# Midi_to_CV.net
KiCad netlist of a schematic drawn in Altium Designer
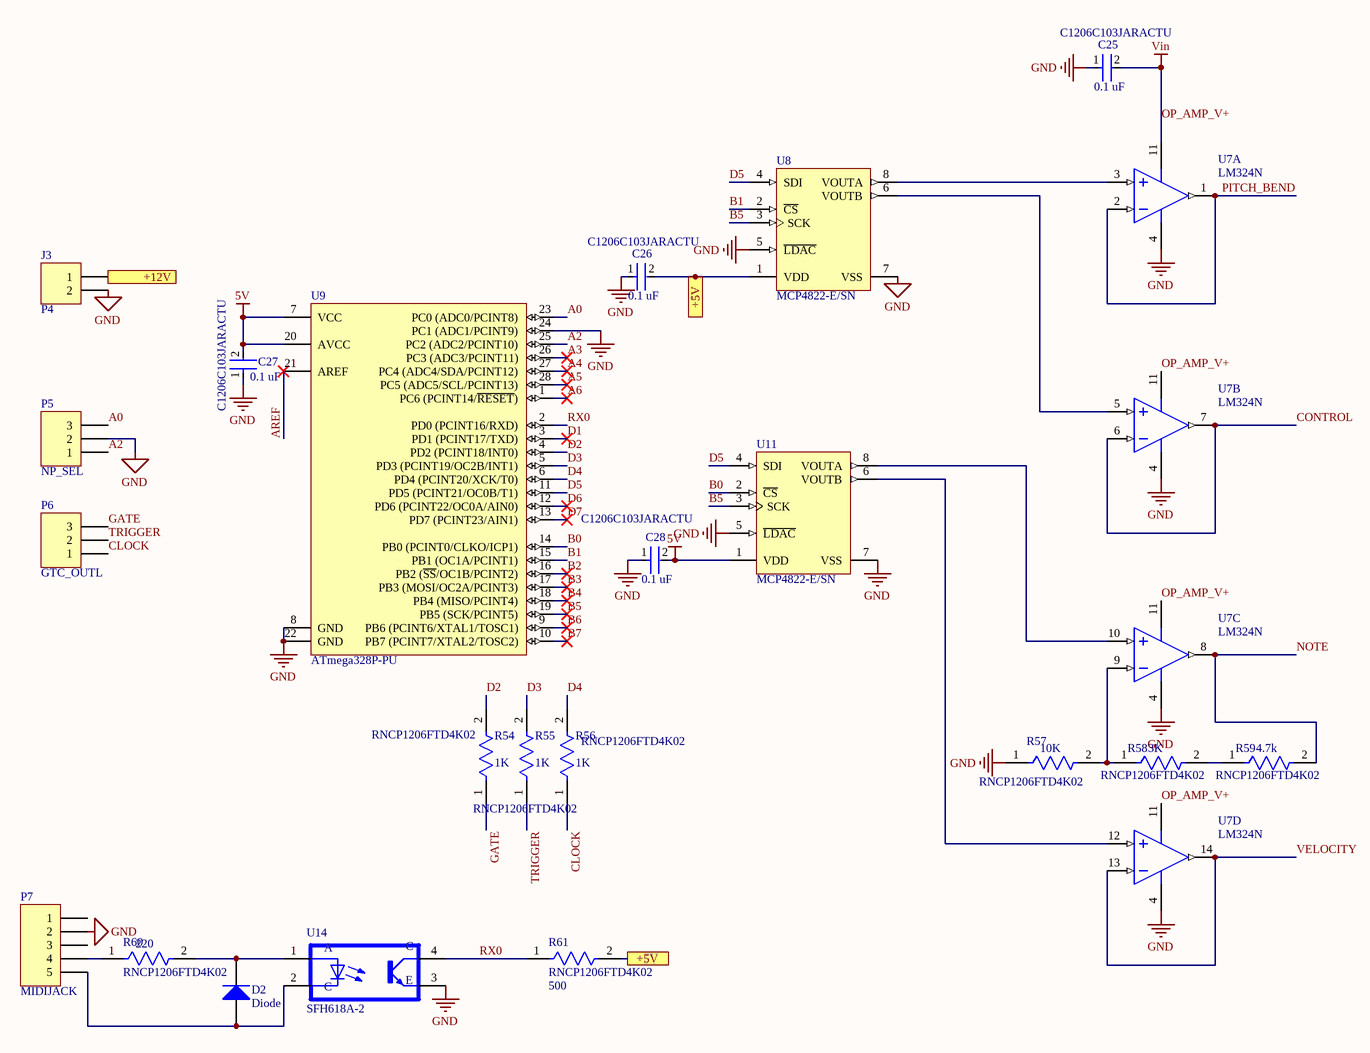
[diagram p0: Midi_to_CV.SchDoc]

(export (version "E")
  (design (tool "Eeschema 10.0.6"))
  (components
    (comp (ref "C25")
      (value "C1206C103JARACTU")
      (footprint "C1206")
      (description "CAP CER 10000PF 250V 5% X7R 1206")
      (fields
        (field (name "TOLERANCE") "0.05")
        (field (name "CAPACITANCE") "0.1 uF")
        (field (name "OCTOPART") "https://octopart.com/c1206c103jaractu-kemet-17306149")
      )
      (libsource (lib "Miscellaneous Devices") (part "b4654b650e69147ec39a6b967a45e02"))
    )
    (comp (ref "C26")
      (value "C1206C103JARACTU")
      (footprint "C1206")
      (description "CAP CER 10000PF 250V 5% X7R 1206")
      (fields
        (field (name "TOLERANCE") "0.05")
        (field (name "CAPACITANCE") "0.1 uF")
        (field (name "OCTOPART") "https://octopart.com/c1206c103jaractu-kemet-17306149")
      )
      (libsource (lib "Miscellaneous Devices") (part "b4654b650e69147ec39a6b967a45e02"))
    )
    (comp (ref "C27")
      (value "C1206C103JARACTU")
      (footprint "C1206")
      (description "CAP CER 10000PF 250V 5% X7R 1206")
      (fields
        (field (name "TOLERANCE") "0.05")
        (field (name "CAPACITANCE") "0.1 uF")
        (field (name "OCTOPART") "https://octopart.com/c1206c103jaractu-kemet-17306149")
      )
      (libsource (lib "Miscellaneous Devices") (part "b4654b650e69147ec39a6b967a45e02"))
    )
    (comp (ref "C28")
      (value "C1206C103JARACTU")
      (footprint "C1206")
      (description "CAP CER 10000PF 250V 5% X7R 1206")
      (fields
        (field (name "TOLERANCE") "0.05")
        (field (name "CAPACITANCE") "0.1 uF")
        (field (name "OCTOPART") "https://octopart.com/c1206c103jaractu-kemet-17306149")
      )
      (libsource (lib "Miscellaneous Devices") (part "b4654b650e69147ec39a6b967a45e02"))
    )
    (comp (ref "D2")
      (value "Diode")
      (footprint "DIODE-0.4")
      (description "Default Diode")
      (fields (field (name "PUBLISHER") "Altium Limited"))
      (libsource (lib "Miscellaneous Devices") (part "Diode"))
    )
    (comp (ref "P4")
      (value "J3")
      (footprint "HDR1X2")
      (description "Header, 2-Pin")
      (fields (field (name "PUBLISHER") "Altium Limited"))
      (libsource (lib "Miscellaneous Connectors") (part "Header 2"))
    )
    (comp (ref "P5")
      (value "NP_SEL")
      (footprint "HDR1X3")
      (description "Header, 3-Pin")
      (fields (field (name "PUBLISHER") "Altium Limited"))
      (libsource (lib "Miscellaneous Connectors") (part "Header 3"))
    )
    (comp (ref "P6")
      (value "GTC_OUTL")
      (footprint "HDR1X3")
      (description "Header, 3-Pin")
      (fields (field (name "PUBLISHER") "Altium Limited"))
      (libsource (lib "Miscellaneous Connectors") (part "Header 3"))
    )
    (comp (ref "P7")
      (value "MIDIJACK")
      (footprint "HDR1X5")
      (description "Header, 5-Pin")
      (fields (field (name "PUBLISHER") "Altium Limited"))
      (libsource (lib "Miscellaneous Connectors") (part "Header 5"))
    )
    (comp (ref "R54")
      (value "RNCP1206FTD4K02")
      (footprint "C1206")
      (description "4.02kΩ ±1% 0.5W 1206 High Power Anti-Sulfur Thin Film Chip Resistor")
      (fields (field (name "RESISTANCE") "1K") (field (name "TOLERANCE") "1%"))
      (libsource (lib "Miscellaneous Devices") (part "1029c3af85768c4190bb7ad29bc67b5"))
    )
    (comp (ref "R55")
      (value "RNCP1206FTD4K02")
      (footprint "C1206")
      (description "4.02kΩ ±1% 0.5W 1206 High Power Anti-Sulfur Thin Film Chip Resistor")
      (fields (field (name "RESISTANCE") "1K") (field (name "TOLERANCE") "1%"))
      (libsource (lib "Miscellaneous Devices") (part "1029c3af85768c4190bb7ad29bc67b5"))
    )
    (comp (ref "R56")
      (value "RNCP1206FTD4K02")
      (footprint "C1206")
      (description "4.02kΩ ±1% 0.5W 1206 High Power Anti-Sulfur Thin Film Chip Resistor")
      (fields (field (name "RESISTANCE") "1K") (field (name "TOLERANCE") "1%"))
      (libsource (lib "Miscellaneous Devices") (part "1029c3af85768c4190bb7ad29bc67b5"))
    )
    (comp (ref "R57")
      (value "RNCP1206FTD4K02")
      (footprint "C1206")
      (description "4.02kΩ ±1% 0.5W 1206 High Power Anti-Sulfur Thin Film Chip Resistor")
      (fields (field (name "RESISTANCE") "10K") (field (name "TOLERANCE") "1%"))
      (libsource (lib "Miscellaneous Devices") (part "1029c3af85768c4190bb7ad29bc67b5"))
    )
    (comp (ref "R58")
      (value "RNCP1206FTD4K02")
      (footprint "C1206")
      (description "4.02kΩ ±1% 0.5W 1206 High Power Anti-Sulfur Thin Film Chip Resistor")
      (fields (field (name "RESISTANCE") "3K") (field (name "TOLERANCE") "1%"))
      (libsource (lib "Miscellaneous Devices") (part "1029c3af85768c4190bb7ad29bc67b5"))
    )
    (comp (ref "R59")
      (value "RNCP1206FTD4K02")
      (footprint "C1206")
      (description "4.02kΩ ±1% 0.5W 1206 High Power Anti-Sulfur Thin Film Chip Resistor")
      (fields (field (name "RESISTANCE") "4.7k") (field (name "TOLERANCE") "1%"))
      (libsource (lib "Miscellaneous Devices") (part "1029c3af85768c4190bb7ad29bc67b5"))
    )
    (comp (ref "R60")
      (value "RNCP1206FTD4K02")
      (footprint "C1206")
      (description "4.02kΩ ±1% 0.5W 1206 High Power Anti-Sulfur Thin Film Chip Resistor")
      (fields (field (name "RESISTANCE") "220") (field (name "TOLERANCE") "1%"))
      (libsource (lib "Miscellaneous Devices") (part "1029c3af85768c4190bb7ad29bc67b5"))
    )
    (comp (ref "R61")
      (value "RNCP1206FTD4K02")
      (footprint "C1206")
      (description "4.02kΩ ±1% 0.5W 1206 High Power Anti-Sulfur Thin Film Chip Resistor")
      (fields (field (name "RESISTANCE") "500") (field (name "TOLERANCE") "1%"))
      (libsource (lib "Miscellaneous Devices") (part "1029c3af85768c4190bb7ad29bc67b5"))
    )
    (comp (ref "U7")
      (value "LM324N")
      (footprint "DIP-14")
      (description "Low Power Quad Operational Amplifier, 14-pin MDIP")
      (fields (field (name "MANUFACTURER") "Texas Instruments"))
      (libsource (lib "61201021621") (part "AMP-OPA-LM124-14"))
    )
    (comp (ref "U8")
      (value "MCP4822-E/SN")
      (footprint "SO8_L")
      (description "12-Bit DACs with Internal VREF and SPI Interface, 8-Pin SOIC 150mil, Extended Temperature")
      (libsource (lib "Miscellaneous Devices") (part "CON-DAC-MCP4822-8"))
    )
    (comp (ref "U9")
      (value "ATmega328P-PU")
      (footprint "DIP787W46P254L3467H508Q28")
      (libsource (lib "Miscellaneous Devices") (part "MC-8B-ATM48-IL28"))
    )
    (comp (ref "U11")
      (value "MCP4822-E/SN")
      (footprint "SO8_L")
      (description "12-Bit DACs with Internal VREF and SPI Interface, 8-Pin SOIC 150mil, Extended Temperature")
      (libsource (lib "Miscellaneous Devices") (part "CON-DAC-MCP4822-8"))
    )
    (comp (ref "U14")
      (value "SFH618A-2")
      (footprint "DIP-4")
      (libsource (lib "Miscellaneous Devices") (part "SFH618A-2"))
    )
  )
  (nets
    (net (code "1") (name "/+5V") (class "Default")
      (node (ref "C26") (pin "2") (pinfunction "2_2") (pintype "passive"))
      (node (ref "R61") (pin "2") (pinfunction "2_2") (pintype "passive"))
      (node (ref "U8") (pin "1") (pinfunction "VDD_1") (pintype "power_in"))
    )
    (net (code "2") (name "/+12V") (class "Default")
      (node (ref "P4") (pin "1") (pinfunction "1_1") (pintype "passive"))
    )
    (net (code "3") (name "/A0") (class "Default")
      (node (ref "P5") (pin "3") (pinfunction "3_3") (pintype "passive"))
      (node (ref "U9") (pin "23") (pinfunction "PC0_(ADC0/PCINT8)_23") (pintype "bidirectional"))
    )
    (net (code "4") (name "/A2") (class "Default")
      (node (ref "P5") (pin "1") (pinfunction "1_1") (pintype "passive"))
      (node (ref "U9") (pin "25") (pinfunction "PC2_(ADC2/PCINT10)_25") (pintype "bidirectional"))
    )
    (net (code "5") (name "/A3") (class "Default")
      (node (ref "U9") (pin "26") (pinfunction "PC3_(ADC3/PCINT11)_26") (pintype "bidirectional+no_connect"))
    )
    (net (code "6") (name "/A4") (class "Default")
      (node (ref "U9") (pin "27") (pinfunction "PC4_(ADC4/SDA/PCINT12)_27") (pintype "bidirectional+no_connect"))
    )
    (net (code "7") (name "/A5") (class "Default")
      (node (ref "U9") (pin "28") (pinfunction "PC5_(ADC5/SCL/PCINT13)_28") (pintype "bidirectional+no_connect"))
    )
    (net (code "8") (name "/A6") (class "Default")
      (node (ref "U9") (pin "1") (pinfunction "PC6_(PCINT14/~{RESET})_1") (pintype "bidirectional+no_connect"))
    )
    (net (code "9") (name "/AREF") (class "Default")
      (node (ref "U9") (pin "21") (pinfunction "AREF_21") (pintype "power_in+no_connect"))
    )
    (net (code "10") (name "/B0") (class "Default")
      (node (ref "U11") (pin "2") (pinfunction "~{CS}_2") (pintype "input"))
      (node (ref "U9") (pin "14") (pinfunction "PB0_(PCINT0/CLKO/ICP1)_14") (pintype "bidirectional"))
    )
    (net (code "11") (name "/B1") (class "Default")
      (node (ref "U8") (pin "2") (pinfunction "~{CS}_2") (pintype "input"))
      (node (ref "U9") (pin "15") (pinfunction "PB1_(OC1A/PCINT1)_15") (pintype "bidirectional"))
    )
    (net (code "12") (name "/B2") (class "Default")
      (node (ref "U9") (pin "16") (pinfunction "PB2_(~{SS}/OC1B/PCINT2)_16") (pintype "bidirectional+no_connect"))
    )
    (net (code "13") (name "/B3") (class "Default")
      (node (ref "U9") (pin "17") (pinfunction "PB3_(MOSI/OC2A/PCINT3)_17") (pintype "bidirectional+no_connect"))
    )
    (net (code "14") (name "/B4") (class "Default")
      (node (ref "U9") (pin "18") (pinfunction "PB4_(MISO/PCINT4)_18") (pintype "bidirectional+no_connect"))
    )
    (net (code "15") (name "/B5") (class "Default")
      (node (ref "U11") (pin "3") (pinfunction "SCK_3") (pintype "input"))
      (node (ref "U8") (pin "3") (pinfunction "SCK_3") (pintype "input"))
      (node (ref "U9") (pin "19") (pinfunction "PB5_(SCK/PCINT5)_19") (pintype "bidirectional"))
    )
    (net (code "16") (name "/B6") (class "Default")
      (node (ref "U9") (pin "9") (pinfunction "PB6_(PCINT6/XTAL1/TOSC1)_9") (pintype "bidirectional+no_connect"))
    )
    (net (code "17") (name "/B7") (class "Default")
      (node (ref "U9") (pin "10") (pinfunction "PB7_(PCINT7/XTAL2/TOSC2)_10") (pintype "bidirectional+no_connect"))
    )
    (net (code "18") (name "/CLOCK") (class "Default")
      (node (ref "P6") (pin "1") (pinfunction "1_1") (pintype "passive"))
      (node (ref "R56") (pin "1") (pinfunction "1_1") (pintype "passive"))
    )
    (net (code "19") (name "/CONTROL") (class "Default")
      (node (ref "U7") (pin "6") (pinfunction "IN2-_6") (pintype "input"))
      (node (ref "U7") (pin "7") (pinfunction "OUT2_7") (pintype "output"))
    )
    (net (code "20") (name "/D1") (class "Default")
      (node (ref "U9") (pin "3") (pinfunction "PD1_(PCINT17/TXD)_3") (pintype "bidirectional+no_connect"))
    )
    (net (code "21") (name "/D2") (class "Default")
      (node (ref "R54") (pin "2") (pinfunction "2_2") (pintype "passive"))
      (node (ref "U9") (pin "4") (pinfunction "PD2_(PCINT18/INT0)_4") (pintype "bidirectional"))
    )
    (net (code "22") (name "/D3") (class "Default")
      (node (ref "R55") (pin "2") (pinfunction "2_2") (pintype "passive"))
      (node (ref "U9") (pin "5") (pinfunction "PD3_(PCINT19/OC2B/INT1)_5") (pintype "bidirectional"))
    )
    (net (code "23") (name "/D4") (class "Default")
      (node (ref "R56") (pin "2") (pinfunction "2_2") (pintype "passive"))
      (node (ref "U9") (pin "6") (pinfunction "PD4_(PCINT20/XCK/T0)_6") (pintype "bidirectional"))
    )
    (net (code "24") (name "/D5") (class "Default")
      (node (ref "U11") (pin "4") (pinfunction "SDI_4") (pintype "input"))
      (node (ref "U8") (pin "4") (pinfunction "SDI_4") (pintype "input"))
      (node (ref "U9") (pin "11") (pinfunction "PD5_(PCINT21/OC0B/T1)_11") (pintype "bidirectional"))
    )
    (net (code "25") (name "/D6") (class "Default")
      (node (ref "U9") (pin "12") (pinfunction "PD6_(PCINT22/OC0A/AIN0)_12") (pintype "bidirectional+no_connect"))
    )
    (net (code "26") (name "/D7") (class "Default")
      (node (ref "U9") (pin "13") (pinfunction "PD7_(PCINT23/AIN1)_13") (pintype "bidirectional+no_connect"))
    )
    (net (code "27") (name "/GATE") (class "Default")
      (node (ref "P6") (pin "3") (pinfunction "3_3") (pintype "passive"))
      (node (ref "R54") (pin "1") (pinfunction "1_1") (pintype "passive"))
    )
    (net (code "28") (name "/NOTE") (class "Default")
      (node (ref "R59") (pin "2") (pinfunction "2_2") (pintype "passive"))
      (node (ref "U7") (pin "8") (pinfunction "OUT3_8") (pintype "output"))
    )
    (net (code "29") (name "/PITCH_BEND") (class "Default")
      (node (ref "U7") (pin "1") (pinfunction "OUT1_1") (pintype "output"))
      (node (ref "U7") (pin "2") (pinfunction "IN1-_2") (pintype "input"))
    )
    (net (code "30") (name "/RX0") (class "Default")
      (node (ref "R61") (pin "1") (pinfunction "1_1") (pintype "passive"))
      (node (ref "U14") (pin "4") (pinfunction "CO_4") (pintype "passive"))
      (node (ref "U9") (pin "2") (pinfunction "PD0_(PCINT16/RXD)_2") (pintype "bidirectional"))
    )
    (net (code "31") (name "/TRIGGER") (class "Default")
      (node (ref "P6") (pin "2") (pinfunction "2_2") (pintype "passive"))
      (node (ref "R55") (pin "1") (pinfunction "1_1") (pintype "passive"))
    )
    (net (code "32") (name "/VELOCITY") (class "Default")
      (node (ref "U7") (pin "13") (pinfunction "IN4-_13") (pintype "input"))
      (node (ref "U7") (pin "14") (pinfunction "OUT4_14") (pintype "output"))
    )
    (net (code "33") (name "5V") (class "Default")
      (node (ref "C27") (pin "2") (pinfunction "2_2") (pintype "passive"))
      (node (ref "C28") (pin "2") (pinfunction "2_2") (pintype "passive"))
      (node (ref "U11") (pin "1") (pinfunction "VDD_1") (pintype "power_in"))
      (node (ref "U9") (pin "20") (pinfunction "AVCC_20") (pintype "power_in"))
      (node (ref "U9") (pin "7") (pinfunction "VCC_7") (pintype "power_in"))
    )
    (net (code "34") (name "GND") (class "Default")
      (node (ref "C25") (pin "1") (pinfunction "1_1") (pintype "passive"))
      (node (ref "C26") (pin "1") (pinfunction "1_1") (pintype "passive"))
      (node (ref "C27") (pin "1") (pinfunction "1_1") (pintype "passive"))
      (node (ref "C28") (pin "1") (pinfunction "1_1") (pintype "passive"))
      (node (ref "P4") (pin "2") (pinfunction "2_2") (pintype "passive"))
      (node (ref "P5") (pin "2") (pinfunction "2_2") (pintype "passive"))
      (node (ref "P7") (pin "2") (pinfunction "2_2") (pintype "passive"))
      (node (ref "R57") (pin "1") (pinfunction "1_1") (pintype "passive"))
      (node (ref "U11") (pin "5") (pinfunction "~{LDAC}_5") (pintype "input"))
      (node (ref "U11") (pin "7") (pinfunction "VSS_7") (pintype "power_in"))
      (node (ref "U14") (pin "3") (pinfunction "E_3") (pintype "passive"))
      (node (ref "U7") (pin "4") (pinfunction "V+_4") (pintype "power_in"))
      (node (ref "U8") (pin "5") (pinfunction "~{LDAC}_5") (pintype "input"))
      (node (ref "U8") (pin "7") (pinfunction "VSS_7") (pintype "power_in"))
      (node (ref "U9") (pin "22") (pinfunction "GND_22") (pintype "power_in"))
      (node (ref "U9") (pin "24") (pinfunction "PC1_(ADC1/PCINT9)_24") (pintype "bidirectional"))
      (node (ref "U9") (pin "8") (pinfunction "GND_8") (pintype "power_in"))
    )
    (net (code "35") (name "Net-(D2-A)") (class "Default")
      (node (ref "D2") (pin "1") (pinfunction "A_1") (pintype "passive"))
      (node (ref "P7") (pin "5") (pinfunction "5_5") (pintype "passive"))
      (node (ref "U14") (pin "2") (pinfunction "C_2") (pintype "passive"))
    )
    (net (code "36") (name "Net-(D2-K)") (class "Default")
      (node (ref "D2") (pin "2") (pinfunction "K_2") (pintype "passive"))
      (node (ref "R60") (pin "2") (pinfunction "2_2") (pintype "passive"))
      (node (ref "U14") (pin "1") (pinfunction "A_1") (pintype "passive"))
    )
    (net (code "37") (name "Net-(P7-Pad4)") (class "Default")
      (node (ref "P7") (pin "4") (pinfunction "4_4") (pintype "passive"))
      (node (ref "R60") (pin "1") (pinfunction "1_1") (pintype "passive"))
    )
    (net (code "38") (name "Net-(R58-Pad2)") (class "Default")
      (node (ref "R58") (pin "2") (pinfunction "2_2") (pintype "passive"))
      (node (ref "R59") (pin "1") (pinfunction "1_1") (pintype "passive"))
    )
    (net (code "39") (name "Net-(U7A-IN1+)") (class "Default")
      (node (ref "U7") (pin "3") (pinfunction "IN1+_3") (pintype "input"))
      (node (ref "U8") (pin "8") (pinfunction "VOUTA_8") (pintype "output"))
    )
    (net (code "40") (name "Net-(U7B-IN2+)") (class "Default")
      (node (ref "U7") (pin "5") (pinfunction "IN2+_5") (pintype "input"))
      (node (ref "U8") (pin "6") (pinfunction "VOUTB_6") (pintype "output"))
    )
    (net (code "41") (name "Net-(U7C-IN3-)") (class "Default")
      (node (ref "R57") (pin "2") (pinfunction "2_2") (pintype "passive"))
      (node (ref "R58") (pin "1") (pinfunction "1_1") (pintype "passive"))
      (node (ref "U7") (pin "9") (pinfunction "IN3-_9") (pintype "input"))
    )
    (net (code "42") (name "Net-(U11-VOUTA)") (class "Default")
      (node (ref "U11") (pin "8") (pinfunction "VOUTA_8") (pintype "output"))
      (node (ref "U7") (pin "10") (pinfunction "IN3+_10") (pintype "input"))
    )
    (net (code "43") (name "Net-(U11-VOUTB)") (class "Default")
      (node (ref "U11") (pin "6") (pinfunction "VOUTB_6") (pintype "output"))
      (node (ref "U7") (pin "12") (pinfunction "IN4+_12") (pintype "input"))
    )
    (net (code "44") (name "Vin") (class "Default")
      (node (ref "C25") (pin "2") (pinfunction "2_2") (pintype "passive"))
      (node (ref "U7") (pin "11") (pinfunction "GND_11") (pintype "power_in"))
    )
    (net (code "45") (name "unconnected-(P7-Pad1)") (class "Default")
      (node (ref "P7") (pin "1") (pinfunction "1_1") (pintype "passive"))
    )
    (net (code "46") (name "unconnected-(P7-Pad3)") (class "Default")
      (node (ref "P7") (pin "3") (pinfunction "3_3") (pintype "passive"))
    )
  )
)
